# rapidshark-half-assed-half-h-bridge-mk-1.net
KiCad netlist of a schematic drawn in EAGLE
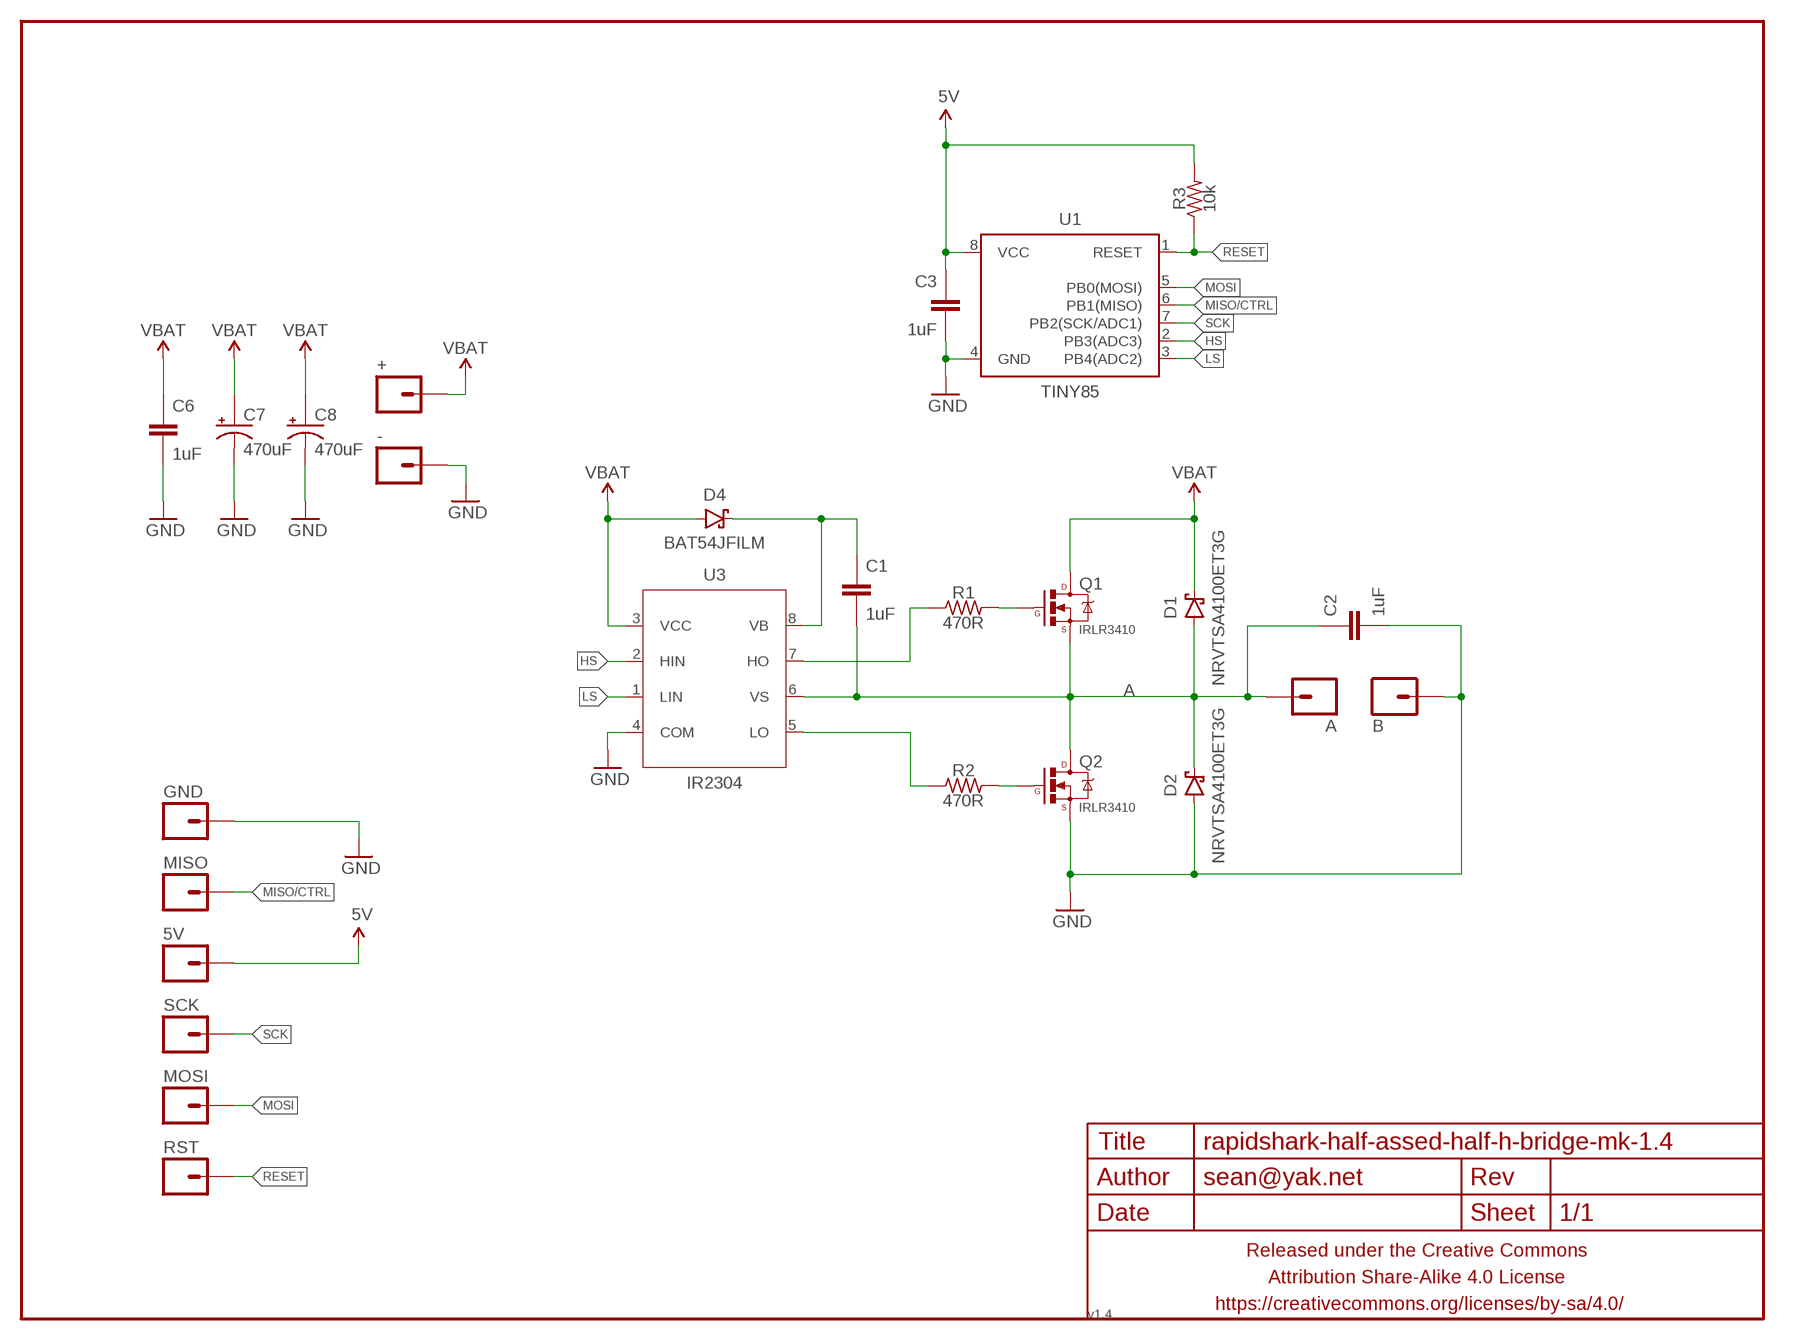
[diagram p0: schematic, sheet 1]

(export (version "E")
  (design (tool "Eeschema 10.0.6"))
  (components
    (comp (ref "+")
      (value "M01PTH-1.4MM")
      (footprint "eagle-import:1X01-1.4MM-CIR")
      (libsource (lib "eagle-import") (part "M01PTH-1.4MM"))
    )
    (comp (ref "-")
      (value "M01PTH-1.4MM")
      (footprint "eagle-import:1X01-1.4MM-CIR")
      (libsource (lib "eagle-import") (part "M01PTH-1.4MM"))
    )
    (comp (ref "5V")
      (value "M01PTH-0.9MM")
      (footprint "eagle-import:1X01-0.9MM")
      (libsource (lib "eagle-import") (part "M01PTH-0.9MM"))
    )
    (comp (ref "A")
      (value "M01PTH-1.4MM")
      (footprint "eagle-import:1X01-1.4MM-CIR")
      (libsource (lib "eagle-import") (part "M01PTH-1.4MM"))
    )
    (comp (ref "B")
      (value "M01PTH-1.4MM")
      (footprint "eagle-import:1X01-1.4MM-CIR")
      (libsource (lib "eagle-import") (part "M01PTH-1.4MM"))
    )
    (comp (ref "C1")
      (value "1uF")
      (footprint "eagle-import:C0603-TIGHTER")
      (libsource (lib "eagle-import") (part "CAPACITOR-CERAMICC0603-TIGHTER"))
    )
    (comp (ref "C2")
      (value "1uF")
      (footprint "eagle-import:C0603-TIGHTER")
      (libsource (lib "eagle-import") (part "CAPACITOR-CERAMICC0603-TIGHTER"))
    )
    (comp (ref "C3")
      (value "1uF")
      (footprint "eagle-import:C0603-TIGHTER")
      (libsource (lib "eagle-import") (part "CAPACITOR-CERAMICC0603-TIGHTER"))
    )
    (comp (ref "C6")
      (value "1uF")
      (footprint "eagle-import:C0603-TIGHTER")
      (libsource (lib "eagle-import") (part "CAPACITOR-CERAMICC0603-TIGHTER"))
    )
    (comp (ref "C7")
      (value "470uF")
      (footprint "eagle-import:E5-10,5")
      (libsource (lib "eagle-import") (part "CAPACITOR-POLARIZEDE5-10.5"))
    )
    (comp (ref "C8")
      (value "470uF")
      (footprint "eagle-import:E5-10,5")
      (libsource (lib "eagle-import") (part "CAPACITOR-POLARIZEDE5-10.5"))
    )
    (comp (ref "D1")
      (value "NRVTSA4100ET3G")
      (footprint "eagle-import:SMA-DIODE-SCHOTTKY")
      (libsource (lib "eagle-import") (part "DIODE-SCHOTTKYSMA"))
    )
    (comp (ref "D2")
      (value "NRVTSA4100ET3G")
      (footprint "eagle-import:SMA-DIODE-SCHOTTKY")
      (libsource (lib "eagle-import") (part "DIODE-SCHOTTKYSMA"))
    )
    (comp (ref "D4")
      (value "BAT54JFILM")
      (footprint "eagle-import:SOD323-SCHOTTKY")
      (libsource (lib "eagle-import") (part "DIODE-SCHOTTKYSOD323"))
    )
    (comp (ref "FRAME1")
      (value "FRAME-LETTERNO_PACKAGE")
      (footprint "eagle-import:DUMMY")
      (fields
        (field (name "DESIGNER") "sean@yak.net")
        (field (name "VERSION") "v1.4")
        (field (name "VERSION_1") "v1.4")
      )
      (libsource (lib "eagle-import") (part "FRAME-LETTERNO_PACKAGE"))
    )
    (comp (ref "GND")
      (value "M01PTH-0.9MM")
      (footprint "eagle-import:1X01-0.9MM")
      (libsource (lib "eagle-import") (part "M01PTH-0.9MM"))
    )
    (comp (ref "MISO")
      (value "M01PTH-0.9MM")
      (footprint "eagle-import:1X01-0.9MM")
      (libsource (lib "eagle-import") (part "M01PTH-0.9MM"))
    )
    (comp (ref "MOSI")
      (value "M01PTH-0.9MM")
      (footprint "eagle-import:1X01-0.9MM")
      (libsource (lib "eagle-import") (part "M01PTH-0.9MM"))
    )
    (comp (ref "Q1")
      (value "IRLR3410")
      (footprint "eagle-import:DPAK")
      (libsource (lib "eagle-import") (part "MOSFET-NCHANNELFDD8780"))
    )
    (comp (ref "Q2")
      (value "IRLR3410")
      (footprint "eagle-import:DPAK")
      (libsource (lib "eagle-import") (part "MOSFET-NCHANNELFDD8780"))
    )
    (comp (ref "R1")
      (value "470R")
      (footprint "eagle-import:R0603-TIGHTER")
      (libsource (lib "eagle-import") (part "RESISTORR0603-TIGHTER"))
    )
    (comp (ref "R2")
      (value "470R")
      (footprint "eagle-import:R0603-TIGHTER")
      (libsource (lib "eagle-import") (part "RESISTORR0603-TIGHTER"))
    )
    (comp (ref "R3")
      (value "10k")
      (footprint "eagle-import:R0603-TIGHTER")
      (libsource (lib "eagle-import") (part "RESISTORR0603-TIGHTER"))
    )
    (comp (ref "RST")
      (value "M01PTH-0.9MM")
      (footprint "eagle-import:1X01-0.9MM")
      (libsource (lib "eagle-import") (part "M01PTH-0.9MM"))
    )
    (comp (ref "SCK")
      (value "M01PTH-0.9MM")
      (footprint "eagle-import:1X01-0.9MM")
      (libsource (lib "eagle-import") (part "M01PTH-0.9MM"))
    )
    (comp (ref "U1")
      (value "TINY85")
      (footprint "eagle-import:SO08-EIAJ")
      (libsource (lib "eagle-import") (part "ATTINY45TINY85-20-SOICW"))
    )
    (comp (ref "U3")
      (value "IR2304")
      (footprint "eagle-import:SO08")
      (libsource (lib "eagle-import") (part "IR2304SSOIC"))
    )
  )
  (nets
    (net (code "1") (name "/A") (class "Default")
      (node (ref "A") (pin "P$1") (pinfunction "1_P$1") (pintype "passive"))
      (node (ref "C1") (pin "2") (pinfunction "2_2") (pintype "passive"))
      (node (ref "C2") (pin "1") (pinfunction "1_1") (pintype "passive"))
      (node (ref "D1") (pin "A") (pinfunction "A_A") (pintype "passive"))
      (node (ref "D2") (pin "C") (pinfunction "C_C") (pintype "passive"))
      (node (ref "Q1") (pin "3") (pinfunction "S_3") (pintype "passive"))
      (node (ref "Q2") (pin "4") (pinfunction "D_4") (pintype "passive"))
      (node (ref "U3") (pin "6") (pinfunction "VS_6") (pintype "passive"))
    )
    (net (code "2") (name "5V") (class "Default")
      (node (ref "5V") (pin "1") (pinfunction "1_1") (pintype "passive"))
      (node (ref "C3") (pin "1") (pinfunction "1_1") (pintype "passive"))
      (node (ref "R3") (pin "2") (pinfunction "2_2") (pintype "passive"))
      (node (ref "U1") (pin "8") (pinfunction "VCC_8") (pintype "bidirectional"))
    )
    (net (code "3") (name "GND") (class "Default")
      (node (ref "-") (pin "P$1") (pinfunction "1_P$1") (pintype "passive"))
      (node (ref "B") (pin "P$1") (pinfunction "1_P$1") (pintype "passive"))
      (node (ref "C2") (pin "2") (pinfunction "2_2") (pintype "passive"))
      (node (ref "C3") (pin "2") (pinfunction "2_2") (pintype "passive"))
      (node (ref "C6") (pin "2") (pinfunction "2_2") (pintype "passive"))
      (node (ref "C7") (pin "-") (pinfunction "-_-") (pintype "passive"))
      (node (ref "C8") (pin "-") (pinfunction "-_-") (pintype "passive"))
      (node (ref "D2") (pin "A") (pinfunction "A_A") (pintype "passive"))
      (node (ref "GND") (pin "1") (pinfunction "1_1") (pintype "passive"))
      (node (ref "Q2") (pin "3") (pinfunction "S_3") (pintype "passive"))
      (node (ref "U1") (pin "4") (pinfunction "GND_4") (pintype "bidirectional"))
      (node (ref "U3") (pin "4") (pinfunction "COM_4") (pintype "passive"))
    )
    (net (code "4") (name "HS") (class "Default")
      (node (ref "U1") (pin "2") (pinfunction "PB3(ADC3)_2") (pintype "bidirectional"))
      (node (ref "U3") (pin "2") (pinfunction "HIN_2") (pintype "passive"))
    )
    (net (code "5") (name "LS") (class "Default")
      (node (ref "U1") (pin "3") (pinfunction "PB4(ADC2)_3") (pintype "bidirectional"))
      (node (ref "U3") (pin "1") (pinfunction "LIN_1") (pintype "passive"))
    )
    (net (code "6") (name "MISO{slash}CTRL") (class "Default")
      (node (ref "MISO") (pin "1") (pinfunction "1_1") (pintype "passive"))
      (node (ref "U1") (pin "6") (pinfunction "PB1(MISO)_6") (pintype "bidirectional"))
    )
    (net (code "7") (name "MOSI") (class "Default")
      (node (ref "MOSI") (pin "1") (pinfunction "1_1") (pintype "passive"))
      (node (ref "U1") (pin "5") (pinfunction "PB0(MOSI)_5") (pintype "bidirectional"))
    )
    (net (code "8") (name "Net-(Q1-G)") (class "Default")
      (node (ref "Q1") (pin "1") (pinfunction "G_1") (pintype "passive"))
      (node (ref "R1") (pin "2") (pinfunction "2_2") (pintype "passive"))
    )
    (net (code "9") (name "Net-(Q2-G)") (class "Default")
      (node (ref "Q2") (pin "1") (pinfunction "G_1") (pintype "passive"))
      (node (ref "R2") (pin "2") (pinfunction "2_2") (pintype "passive"))
    )
    (net (code "10") (name "Net-(U3-HO)") (class "Default")
      (node (ref "R1") (pin "1") (pinfunction "1_1") (pintype "passive"))
      (node (ref "U3") (pin "7") (pinfunction "HO_7") (pintype "passive"))
    )
    (net (code "11") (name "Net-(U3-LO)") (class "Default")
      (node (ref "R2") (pin "1") (pinfunction "1_1") (pintype "passive"))
      (node (ref "U3") (pin "5") (pinfunction "LO_5") (pintype "passive"))
    )
    (net (code "12") (name "Net-(U3-VB)") (class "Default")
      (node (ref "C1") (pin "1") (pinfunction "1_1") (pintype "passive"))
      (node (ref "D4") (pin "C") (pinfunction "C_C") (pintype "passive"))
      (node (ref "U3") (pin "8") (pinfunction "VB_8") (pintype "passive"))
    )
    (net (code "13") (name "RESET") (class "Default")
      (node (ref "R3") (pin "1") (pinfunction "1_1") (pintype "passive"))
      (node (ref "RST") (pin "1") (pinfunction "1_1") (pintype "passive"))
      (node (ref "U1") (pin "1") (pinfunction "RESET_1") (pintype "bidirectional"))
    )
    (net (code "14") (name "SCK") (class "Default")
      (node (ref "SCK") (pin "1") (pinfunction "1_1") (pintype "passive"))
      (node (ref "U1") (pin "7") (pinfunction "PB2(SCK/ADC1)_7") (pintype "bidirectional"))
    )
    (net (code "15") (name "VBAT") (class "Default")
      (node (ref "+") (pin "P$1") (pinfunction "1_P$1") (pintype "passive"))
      (node (ref "C6") (pin "1") (pinfunction "1_1") (pintype "passive"))
      (node (ref "C7") (pin "+") (pinfunction "+_+") (pintype "passive"))
      (node (ref "C8") (pin "+") (pinfunction "+_+") (pintype "passive"))
      (node (ref "D1") (pin "C") (pinfunction "C_C") (pintype "passive"))
      (node (ref "D4") (pin "A") (pinfunction "A_A") (pintype "passive"))
      (node (ref "Q1") (pin "4") (pinfunction "D_4") (pintype "passive"))
      (node (ref "U3") (pin "3") (pinfunction "VCC_3") (pintype "passive"))
    )
  )
)
